# Hheld-Sheet1.net
KiCad netlist of a schematic drawn in Altium Designer
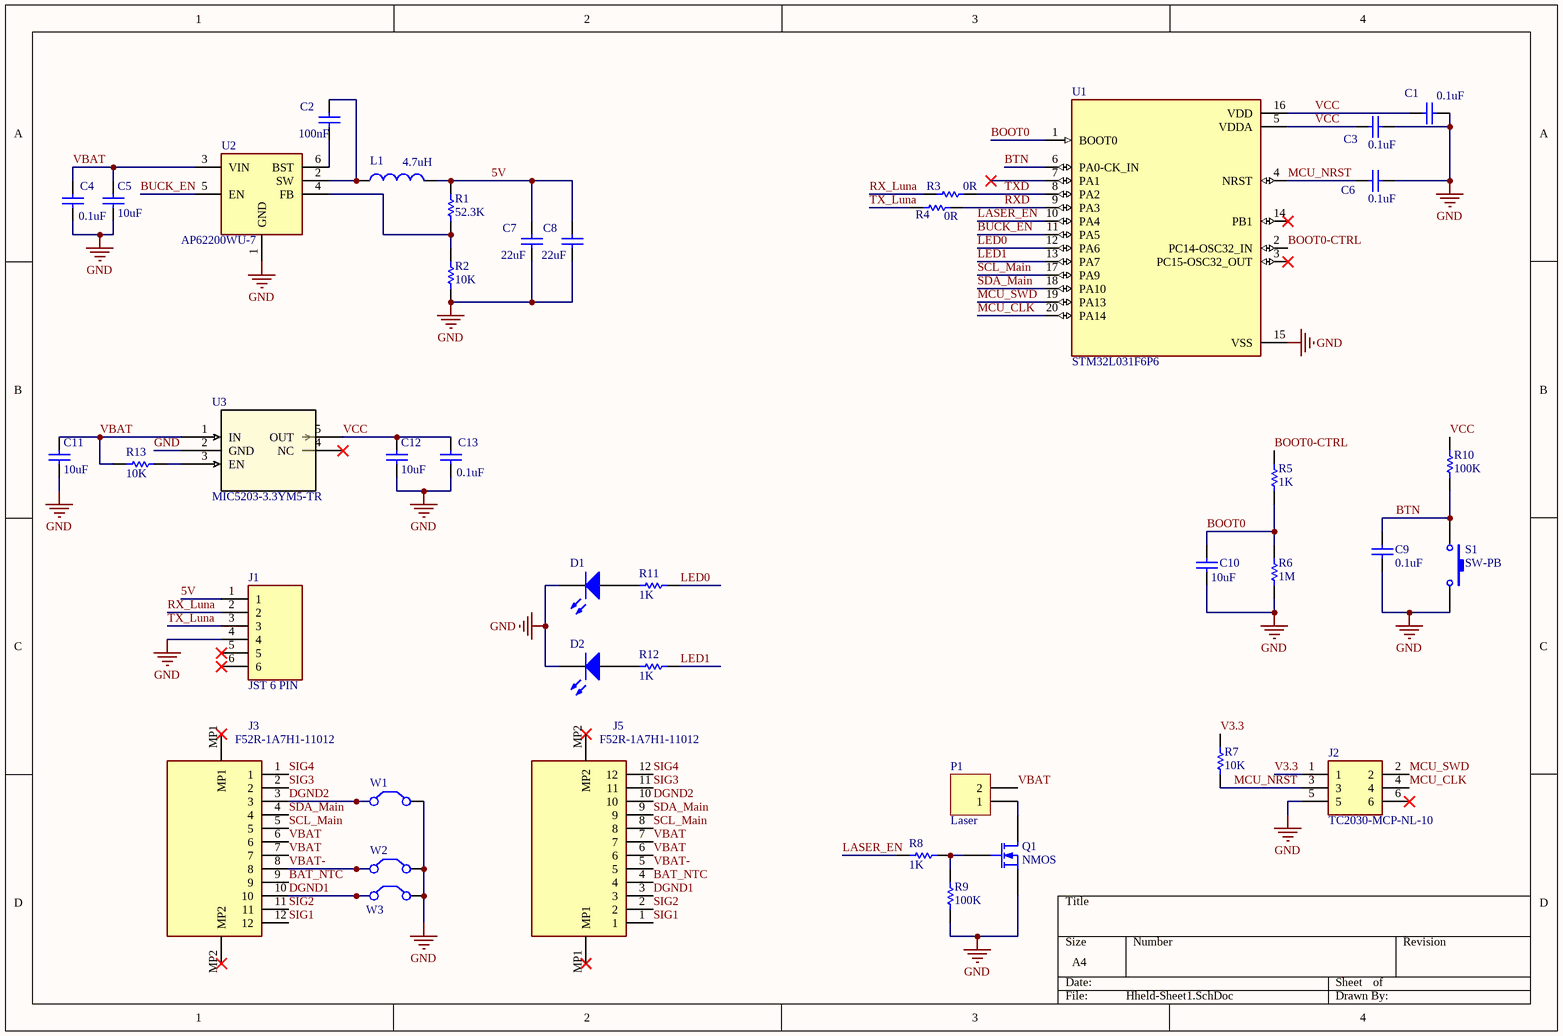
[diagram p0: Hheld-Sheet1.SchDoc]

(export (version "E")
  (design (tool "Eeschema 10.0.6"))
  (components
    (comp (ref "C1")
      (value "0.1uF")
      (footprint "Miscellaneous Devices:0402")
      (description "Capacitor")
      (fields (field (name "PUBLISHER") "Altium Limited"))
      (libsource (lib "Miscellaneous Devices") (part "Cap"))
    )
    (comp (ref "C2")
      (value "100nF")
      (footprint "Miscellaneous Devices:0402")
      (description "Capacitor")
      (fields (field (name "PUBLISHER") "Altium Limited"))
      (libsource (lib "Miscellaneous Devices") (part "Cap"))
    )
    (comp (ref "C3")
      (value "0.1uF")
      (footprint "Miscellaneous Devices:0402")
      (description "Capacitor")
      (fields (field (name "PUBLISHER") "Altium Limited"))
      (libsource (lib "Miscellaneous Devices") (part "Cap"))
    )
    (comp (ref "C4")
      (value "0.1uF")
      (footprint "Miscellaneous Devices:0402")
      (description "Capacitor")
      (fields (field (name "PUBLISHER") "Altium Limited"))
      (libsource (lib "Miscellaneous Devices") (part "Cap"))
    )
    (comp (ref "C5")
      (value "10uF")
      (footprint "Miscellaneous Devices:6-0805_L")
      (description "Capacitor")
      (fields (field (name "PUBLISHER") "Altium Limited"))
      (libsource (lib "Miscellaneous Devices") (part "Cap"))
    )
    (comp (ref "C6")
      (value "0.1uF")
      (footprint "Miscellaneous Devices:0402")
      (description "Capacitor")
      (fields (field (name "PUBLISHER") "Altium Limited"))
      (libsource (lib "Miscellaneous Devices") (part "Cap"))
    )
    (comp (ref "C7")
      (value "22uF")
      (footprint "Miscellaneous Devices:6-0805_L")
      (description "Capacitor")
      (fields (field (name "PUBLISHER") "Altium Limited"))
      (libsource (lib "Miscellaneous Devices") (part "Cap"))
    )
    (comp (ref "C8")
      (value "22uF")
      (footprint "Miscellaneous Devices:6-0805_L")
      (description "Capacitor")
      (fields (field (name "PUBLISHER") "Altium Limited"))
      (libsource (lib "Miscellaneous Devices") (part "Cap"))
    )
    (comp (ref "C9")
      (value "0.1uF")
      (footprint "Miscellaneous Devices:0402")
      (description "Capacitor")
      (fields (field (name "PUBLISHER") "Altium Limited"))
      (libsource (lib "Miscellaneous Devices") (part "Cap"))
    )
    (comp (ref "C10")
      (value "10uF")
      (footprint "Miscellaneous Devices:6-0805_L")
      (description "Capacitor")
      (fields (field (name "PUBLISHER") "Altium Limited"))
      (libsource (lib "Miscellaneous Devices") (part "Cap"))
    )
    (comp (ref "C11")
      (value "10uF")
      (footprint "Miscellaneous Devices:6-0805_L")
      (description "Capacitor")
      (fields (field (name "PUBLISHER") "Altium Limited"))
      (libsource (lib "Miscellaneous Devices") (part "Cap"))
    )
    (comp (ref "C12")
      (value "10uF")
      (footprint "Miscellaneous Devices:6-0805_L")
      (description "Capacitor")
      (fields (field (name "PUBLISHER") "Altium Limited"))
      (libsource (lib "Miscellaneous Devices") (part "Cap"))
    )
    (comp (ref "C13")
      (value "0.1uF")
      (footprint "Miscellaneous Devices:0402")
      (description "Capacitor")
      (fields (field (name "PUBLISHER") "Altium Limited"))
      (libsource (lib "Miscellaneous Devices") (part "Cap"))
    )
    (comp (ref "D1")
      (value "~")
      (footprint "1608[0603]")
      (description "Typical INFRARED GaAs LED")
      (fields (field (name "PUBLISHER") "Altium Limited"))
      (libsource (lib "Miscellaneous Devices") (part "LED0"))
    )
    (comp (ref "D2")
      (value "~")
      (footprint "1608[0603]")
      (description "Typical INFRARED GaAs LED")
      (fields (field (name "PUBLISHER") "Altium Limited"))
      (libsource (lib "Miscellaneous Devices") (part "LED0"))
    )
    (comp (ref "J1")
      (value "JST 6 PIN")
      (footprint "SHDRRA6W50P0X200_1X6_1390X760X480P")
      (description "Connector")
      (fields (field (name "MANUFACTURER_PART_NUMBER") "S6B-PH-K-S(LF)(SN)"))
      (libsource (lib "S6B-PH-K-S(LF)(SN) JST 6PIN") (part "S6B-PH-K-S_LF__SN_"))
    )
    (comp (ref "J2")
      (value "TC2030-MCP-NL-10")
      (footprint "TC2030MCPNL10")
      (description "Connector")
      (libsource (lib "TC2030") (part "TC2030-MCP-NL-10"))
    )
    (comp (ref "J3")
      (value "F52R-1A7H1-11012")
      (footprint "F52R1A7H111012")
      (description "Connector")
      (libsource (lib "") (part "F52R-1A7H1-11012_1"))
    )
    (comp (ref "J5")
      (value "F52R-1A7H1-11012")
      (footprint "F52R1A7H111012")
      (description "Connector")
      (libsource (lib "F52R-1A7H1-11012 FPC") (part "F52R-1A7H1-11012"))
    )
    (comp (ref "L1")
      (value "4.7uH")
      (footprint "TYS50404R7N-10 inductor:TYS50404R7N10")
      (description "Inductor")
      (fields (field (name "PUBLISHER") "Altium Limited"))
      (libsource (lib "Miscellaneous Devices") (part "Inductor"))
    )
    (comp (ref "P1")
      (value "Laser")
      (footprint "MHDR1X2")
      (description "Header, 2-Pin")
      (fields (field (name "PUBLISHER") "Altium Limited"))
      (libsource (lib "Miscellaneous Connectors") (part "MHDR1X2"))
    )
    (comp (ref "Q1")
      (value "NMOS")
      (footprint "SOT65P210X100-3N")
      (description "N-Channel MOSFETBSS214NWH6327XTSA1")
      (fields (field (name "PUBLISHER") "Altium Limited"))
      (libsource (lib "Miscellaneous Devices") (part "MOSFET-N"))
    )
    (comp (ref "R1")
      (value "52.3K")
      (footprint "Miscellaneous Devices:0402")
      (description "Semiconductor Resistor")
      (fields (field (name "PUBLISHER") "Altium Limited"))
      (libsource (lib "Miscellaneous Devices") (part "Res Semi"))
    )
    (comp (ref "R2")
      (value "10K")
      (footprint "Miscellaneous Devices:0402")
      (description "Semiconductor Resistor")
      (fields (field (name "PUBLISHER") "Altium Limited"))
      (libsource (lib "Miscellaneous Devices") (part "Res Semi"))
    )
    (comp (ref "R3")
      (value "0R")
      (footprint "Miscellaneous Devices:0402")
      (description "Semiconductor Resistor")
      (fields (field (name "PUBLISHER") "Altium Limited"))
      (libsource (lib "Miscellaneous Devices") (part "Res Semi"))
    )
    (comp (ref "R4")
      (value "0R")
      (footprint "Miscellaneous Devices:0402")
      (description "Semiconductor Resistor")
      (fields (field (name "PUBLISHER") "Altium Limited"))
      (libsource (lib "Miscellaneous Devices") (part "Res Semi"))
    )
    (comp (ref "R5")
      (value "1K")
      (footprint "Miscellaneous Devices:0402")
      (description "Semiconductor Resistor")
      (fields (field (name "PUBLISHER") "Altium Limited"))
      (libsource (lib "Miscellaneous Devices") (part "Res Semi"))
    )
    (comp (ref "R6")
      (value "1M")
      (footprint "Miscellaneous Devices:0402")
      (description "Semiconductor Resistor")
      (fields (field (name "PUBLISHER") "Altium Limited"))
      (libsource (lib "Miscellaneous Devices") (part "Res Semi"))
    )
    (comp (ref "R7")
      (value "10K")
      (footprint "Miscellaneous Devices:0402")
      (description "Semiconductor Resistor")
      (fields (field (name "PUBLISHER") "Altium Limited"))
      (libsource (lib "Miscellaneous Devices") (part "Res Semi"))
    )
    (comp (ref "R8")
      (value "1K")
      (footprint "Miscellaneous Devices:0402")
      (description "Semiconductor Resistor")
      (fields (field (name "PUBLISHER") "Altium Limited"))
      (libsource (lib "Miscellaneous Devices") (part "Res Semi"))
    )
    (comp (ref "R9")
      (value "100K")
      (footprint "Miscellaneous Devices:0402")
      (description "Semiconductor Resistor")
      (fields (field (name "PUBLISHER") "Altium Limited"))
      (libsource (lib "Miscellaneous Devices") (part "Res Semi"))
    )
    (comp (ref "R10")
      (value "100K")
      (footprint "Miscellaneous Devices:0402")
      (description "Semiconductor Resistor")
      (fields (field (name "PUBLISHER") "Altium Limited"))
      (libsource (lib "Miscellaneous Devices") (part "Res Semi"))
    )
    (comp (ref "R11")
      (value "1K")
      (footprint "Miscellaneous Devices:0402")
      (description "Semiconductor Resistor")
      (fields (field (name "PUBLISHER") "Altium Limited"))
      (libsource (lib "Miscellaneous Devices") (part "Res Semi"))
    )
    (comp (ref "R12")
      (value "1K")
      (footprint "Miscellaneous Devices:0402")
      (description "Semiconductor Resistor")
      (fields (field (name "PUBLISHER") "Altium Limited"))
      (libsource (lib "Miscellaneous Devices") (part "Res Semi"))
    )
    (comp (ref "R13")
      (value "10K")
      (footprint "Miscellaneous Devices:0402")
      (description "Semiconductor Resistor")
      (fields (field (name "PUBLISHER") "Altium Limited"))
      (libsource (lib "Miscellaneous Devices") (part "Res Semi"))
    )
    (comp (ref "S1")
      (value "SW-PB")
      (footprint "430456085736")
      (description "Switch")
      (fields (field (name "PUBLISHER") "Altium Limited"))
      (libsource (lib "Miscellaneous Devices") (part "SW-PB"))
    )
    (comp (ref "U1")
      (value "STM32L031F6P6")
      (footprint "SOP65P640X120-20N")
      (description "Ultra-low-power ARM Cortex-M0+ MCU with 32-Kbytes Flash, 32 MHz CPU")
      (fields (field (name "MF") "{'manufacturer': u'STMicroelectronics'}"))
      (libsource (lib "*") (part "STM32L031F6P6"))
    )
    (comp (ref "U2")
      (value "AP62200WU-7")
      (footprint "SOT95P280X100-6N")
      (description "Integrated Circuit")
      (fields (field (name "MOUSER PART NUMBER") "621-AP62200WU-7"))
      (libsource (lib "AP62200WU-7 DC-DC") (part "AP62200WU-7"))
    )
    (comp (ref "U3")
      (value "MIC5203-3.3YM5-TR")
      (footprint "SOT-23-5_M5_MCH")
      (description "No Description Available")
      (fields (field (name "COPYRIGHT") "Copyright (C) 2022 Ultra Librarian. All rights reserved."))
      (libsource (lib "MIC5203-3P3YM5-TR") (part "MIC5203-3.3YM5-TR"))
    )
    (comp (ref "W1")
      (value "~")
      (footprint "0402")
      (description "Jumper Wire")
      (fields (field (name "PUBLISHER") "Altium Limited"))
      (libsource (lib "Miscellaneous Devices") (part "Jumper"))
    )
    (comp (ref "W2")
      (value "~")
      (footprint "0402")
      (description "Jumper Wire")
      (fields (field (name "PUBLISHER") "Altium Limited"))
      (libsource (lib "Miscellaneous Devices") (part "Jumper"))
    )
    (comp (ref "W3")
      (value "~")
      (footprint "0402")
      (description "Jumper Wire")
      (fields (field (name "PUBLISHER") "Altium Limited"))
      (libsource (lib "Miscellaneous Devices") (part "Jumper"))
    )
  )
  (nets
    (net (code "1") (name "/5V") (class "Default")
      (node (ref "C7") (pin "1") (pinfunction "1_1") (pintype "passive"))
      (node (ref "C8") (pin "1") (pinfunction "1_1") (pintype "passive"))
      (node (ref "J1") (pin "1") (pinfunction "1_1") (pintype "passive"))
      (node (ref "L1") (pin "2") (pinfunction "2_2") (pintype "passive"))
      (node (ref "R1") (pin "2") (pinfunction "2_2") (pintype "passive"))
    )
    (net (code "2") (name "/BAT_NTC") (class "Default")
      (node (ref "J3") (pin "9") (pinfunction "9_9") (pintype "passive"))
      (node (ref "J5") (pin "4") (pinfunction "4_4") (pintype "passive"))
    )
    (net (code "3") (name "/BOOT0") (class "Default")
      (node (ref "C10") (pin "2") (pinfunction "2_2") (pintype "passive"))
      (node (ref "R5") (pin "1") (pinfunction "1_1") (pintype "passive"))
      (node (ref "R6") (pin "2") (pinfunction "2_2") (pintype "passive"))
      (node (ref "U1") (pin "1") (pinfunction "BOOT0_1") (pintype "input"))
    )
    (net (code "4") (name "/BOOT0-CTRL") (class "Default")
      (node (ref "R5") (pin "2") (pinfunction "2_2") (pintype "passive"))
      (node (ref "U1") (pin "2") (pinfunction "PC14-OSC32_IN_2") (pintype "bidirectional"))
    )
    (net (code "5") (name "/BTN") (class "Default")
      (node (ref "C9") (pin "1") (pinfunction "1_1") (pintype "passive"))
      (node (ref "R10") (pin "1") (pinfunction "1_1") (pintype "passive"))
      (node (ref "S1") (pin "1") (pinfunction "1_1") (pintype "passive"))
      (node (ref "U1") (pin "6") (pinfunction "PA0-CK_IN_6") (pintype "bidirectional"))
    )
    (net (code "6") (name "/BUCK_EN") (class "Default")
      (node (ref "U1") (pin "11") (pinfunction "PA5_11") (pintype "bidirectional"))
      (node (ref "U2") (pin "5") (pinfunction "EN_5") (pintype "passive"))
    )
    (net (code "7") (name "/DGND1") (class "Default")
      (node (ref "J3") (pin "10") (pinfunction "10_10") (pintype "passive"))
      (node (ref "J5") (pin "3") (pinfunction "3_3") (pintype "passive"))
      (node (ref "W3") (pin "1") (pinfunction "C1_1") (pintype "passive"))
    )
    (net (code "8") (name "/DGND2") (class "Default")
      (node (ref "J3") (pin "3") (pinfunction "3_3") (pintype "passive"))
      (node (ref "J5") (pin "10") (pinfunction "10_10") (pintype "passive"))
      (node (ref "W1") (pin "1") (pinfunction "C1_1") (pintype "passive"))
    )
    (net (code "9") (name "/LASER_EN") (class "Default")
      (node (ref "R8") (pin "1") (pinfunction "1_1") (pintype "passive"))
      (node (ref "U1") (pin "10") (pinfunction "PA4_10") (pintype "bidirectional"))
    )
    (net (code "10") (name "/LED0") (class "Default")
      (node (ref "R11") (pin "2") (pinfunction "2_2") (pintype "passive"))
      (node (ref "U1") (pin "12") (pinfunction "PA6_12") (pintype "bidirectional"))
    )
    (net (code "11") (name "/LED1") (class "Default")
      (node (ref "R12") (pin "2") (pinfunction "2_2") (pintype "passive"))
      (node (ref "U1") (pin "13") (pinfunction "PA7_13") (pintype "bidirectional"))
    )
    (net (code "12") (name "/MCU_CLK") (class "Default")
      (node (ref "J2") (pin "4") (pinfunction "4_4") (pintype "passive"))
      (node (ref "U1") (pin "20") (pinfunction "PA14_20") (pintype "bidirectional"))
    )
    (net (code "13") (name "/MCU_NRST") (class "Default")
      (node (ref "C6") (pin "1") (pinfunction "1_1") (pintype "passive"))
      (node (ref "J2") (pin "3") (pinfunction "3_3") (pintype "passive"))
      (node (ref "R7") (pin "1") (pinfunction "1_1") (pintype "passive"))
      (node (ref "U1") (pin "4") (pinfunction "NRST_4") (pintype "bidirectional"))
    )
    (net (code "14") (name "/MCU_SWD") (class "Default")
      (node (ref "J2") (pin "2") (pinfunction "2_2") (pintype "passive"))
      (node (ref "U1") (pin "19") (pinfunction "PA13_19") (pintype "bidirectional"))
    )
    (net (code "15") (name "/RXD") (class "Default")
      (node (ref "R4") (pin "1") (pinfunction "1_1") (pintype "passive"))
      (node (ref "U1") (pin "9") (pinfunction "PA3_9") (pintype "bidirectional"))
    )
    (net (code "16") (name "/RX_Luna") (class "Default")
      (node (ref "J1") (pin "2") (pinfunction "2_2") (pintype "passive"))
      (node (ref "R3") (pin "2") (pinfunction "2_2") (pintype "passive"))
    )
    (net (code "17") (name "/SCL_Main") (class "Default")
      (node (ref "J3") (pin "5") (pinfunction "5_5") (pintype "passive"))
      (node (ref "J5") (pin "8") (pinfunction "8_8") (pintype "passive"))
      (node (ref "U1") (pin "17") (pinfunction "PA9_17") (pintype "bidirectional"))
    )
    (net (code "18") (name "/SDA_Main") (class "Default")
      (node (ref "J3") (pin "4") (pinfunction "4_4") (pintype "passive"))
      (node (ref "J5") (pin "9") (pinfunction "9_9") (pintype "passive"))
      (node (ref "U1") (pin "18") (pinfunction "PA10_18") (pintype "bidirectional"))
    )
    (net (code "19") (name "/SIG1") (class "Default")
      (node (ref "J3") (pin "12") (pinfunction "12_12") (pintype "passive"))
      (node (ref "J5") (pin "1") (pinfunction "1_1") (pintype "passive"))
    )
    (net (code "20") (name "/SIG2") (class "Default")
      (node (ref "J3") (pin "11") (pinfunction "11_11") (pintype "passive"))
      (node (ref "J5") (pin "2") (pinfunction "2_2") (pintype "passive"))
    )
    (net (code "21") (name "/SIG3") (class "Default")
      (node (ref "J3") (pin "2") (pinfunction "2_2") (pintype "passive"))
      (node (ref "J5") (pin "11") (pinfunction "11_11") (pintype "passive"))
    )
    (net (code "22") (name "/SIG4") (class "Default")
      (node (ref "J3") (pin "1") (pinfunction "1_1") (pintype "passive"))
      (node (ref "J5") (pin "12") (pinfunction "12_12") (pintype "passive"))
    )
    (net (code "23") (name "/TXD") (class "Default")
      (node (ref "R3") (pin "1") (pinfunction "1_1") (pintype "passive"))
      (node (ref "U1") (pin "8") (pinfunction "PA2_8") (pintype "bidirectional"))
    )
    (net (code "24") (name "/TX_Luna") (class "Default")
      (node (ref "J1") (pin "3") (pinfunction "3_3") (pintype "passive"))
      (node (ref "R4") (pin "2") (pinfunction "2_2") (pintype "passive"))
    )
    (net (code "25") (name "/V3.3") (class "Default")
      (node (ref "J2") (pin "1") (pinfunction "1_1") (pintype "passive"))
      (node (ref "R7") (pin "2") (pinfunction "2_2") (pintype "passive"))
    )
    (net (code "26") (name "/VBAT") (class "Default")
      (node (ref "C11") (pin "2") (pinfunction "2_2") (pintype "passive"))
      (node (ref "C4") (pin "2") (pinfunction "2_2") (pintype "passive"))
      (node (ref "C5") (pin "2") (pinfunction "2_2") (pintype "passive"))
      (node (ref "J3") (pin "6") (pinfunction "6_6") (pintype "passive"))
      (node (ref "J3") (pin "7") (pinfunction "7_7") (pintype "passive"))
      (node (ref "J5") (pin "6") (pinfunction "6_6") (pintype "passive"))
      (node (ref "J5") (pin "7") (pinfunction "7_7") (pintype "passive"))
      (node (ref "P1") (pin "2") (pinfunction "2_2") (pintype "passive"))
      (node (ref "R13") (pin "1") (pinfunction "1_1") (pintype "passive"))
      (node (ref "U2") (pin "3") (pinfunction "VIN_3") (pintype "passive"))
      (node (ref "U3") (pin "1") (pinfunction "IN_1") (pintype "input"))
    )
    (net (code "27") (name "/VBAT-") (class "Default")
      (node (ref "J3") (pin "8") (pinfunction "8_8") (pintype "passive"))
      (node (ref "J5") (pin "5") (pinfunction "5_5") (pintype "passive"))
      (node (ref "W2") (pin "1") (pinfunction "C1_1") (pintype "passive"))
    )
    (net (code "28") (name "/VCC") (class "Default")
      (node (ref "C1") (pin "1") (pinfunction "1_1") (pintype "passive"))
      (node (ref "C12") (pin "2") (pinfunction "2_2") (pintype "passive"))
      (node (ref "C13") (pin "2") (pinfunction "2_2") (pintype "passive"))
      (node (ref "C3") (pin "1") (pinfunction "1_1") (pintype "passive"))
      (node (ref "R10") (pin "2") (pinfunction "2_2") (pintype "passive"))
      (node (ref "U1") (pin "16") (pinfunction "VDD_16") (pintype "power_in"))
      (node (ref "U1") (pin "5") (pinfunction "VDDA_5") (pintype "power_in"))
      (node (ref "U3") (pin "5") (pinfunction "OUT_5") (pintype "passive"))
    )
    (net (code "29") (name "GND") (class "Default")
      (node (ref "C1") (pin "2") (pinfunction "2_2") (pintype "passive"))
      (node (ref "C10") (pin "1") (pinfunction "1_1") (pintype "passive"))
      (node (ref "C11") (pin "1") (pinfunction "1_1") (pintype "passive"))
      (node (ref "C12") (pin "1") (pinfunction "1_1") (pintype "passive"))
      (node (ref "C13") (pin "1") (pinfunction "1_1") (pintype "passive"))
      (node (ref "C3") (pin "2") (pinfunction "2_2") (pintype "passive"))
      (node (ref "C4") (pin "1") (pinfunction "1_1") (pintype "passive"))
      (node (ref "C5") (pin "1") (pinfunction "1_1") (pintype "passive"))
      (node (ref "C6") (pin "2") (pinfunction "2_2") (pintype "passive"))
      (node (ref "C7") (pin "2") (pinfunction "2_2") (pintype "passive"))
      (node (ref "C8") (pin "2") (pinfunction "2_2") (pintype "passive"))
      (node (ref "C9") (pin "2") (pinfunction "2_2") (pintype "passive"))
      (node (ref "D1") (pin "2") (pinfunction "K_2") (pintype "passive"))
      (node (ref "D2") (pin "2") (pinfunction "K_2") (pintype "passive"))
      (node (ref "J1") (pin "4") (pinfunction "4_4") (pintype "passive"))
      (node (ref "J2") (pin "5") (pinfunction "5_5") (pintype "passive"))
      (node (ref "Q1") (pin "3") (pinfunction "S_3") (pintype "passive"))
      (node (ref "R2") (pin "2") (pinfunction "2_2") (pintype "passive"))
      (node (ref "R6") (pin "1") (pinfunction "1_1") (pintype "passive"))
      (node (ref "R9") (pin "1") (pinfunction "1_1") (pintype "passive"))
      (node (ref "S1") (pin "2") (pinfunction "2_2") (pintype "passive"))
      (node (ref "U1") (pin "15") (pinfunction "VSS_15") (pintype "power_in"))
      (node (ref "U2") (pin "1") (pinfunction "GND_1") (pintype "passive"))
      (node (ref "U3") (pin "2") (pinfunction "GND_2") (pintype "power_in"))
      (node (ref "W1") (pin "2") (pinfunction "C2_2") (pintype "passive"))
      (node (ref "W2") (pin "2") (pinfunction "C2_2") (pintype "passive"))
      (node (ref "W3") (pin "2") (pinfunction "C2_2") (pintype "passive"))
    )
    (net (code "30") (name "Net-(D1-A)") (class "Default")
      (node (ref "D1") (pin "1") (pinfunction "A_1") (pintype "passive"))
      (node (ref "R11") (pin "1") (pinfunction "1_1") (pintype "passive"))
    )
    (net (code "31") (name "Net-(D2-A)") (class "Default")
      (node (ref "D2") (pin "1") (pinfunction "A_1") (pintype "passive"))
      (node (ref "R12") (pin "1") (pinfunction "1_1") (pintype "passive"))
    )
    (net (code "32") (name "Net-(Q1-D)") (class "Default")
      (node (ref "P1") (pin "1") (pinfunction "1_1") (pintype "passive"))
      (node (ref "Q1") (pin "1") (pinfunction "D_1") (pintype "passive"))
    )
    (net (code "33") (name "Net-(Q1-G)") (class "Default")
      (node (ref "Q1") (pin "2") (pinfunction "G_2") (pintype "passive"))
      (node (ref "R8") (pin "2") (pinfunction "2_2") (pintype "passive"))
      (node (ref "R9") (pin "2") (pinfunction "2_2") (pintype "passive"))
    )
    (net (code "34") (name "Net-(U2-BST)") (class "Default")
      (node (ref "C2") (pin "2") (pinfunction "2_2") (pintype "passive"))
      (node (ref "U2") (pin "6") (pinfunction "BST_6") (pintype "passive"))
    )
    (net (code "35") (name "Net-(U2-FB)") (class "Default")
      (node (ref "R1") (pin "1") (pinfunction "1_1") (pintype "passive"))
      (node (ref "R2") (pin "1") (pinfunction "1_1") (pintype "passive"))
      (node (ref "U2") (pin "4") (pinfunction "FB_4") (pintype "passive"))
    )
    (net (code "36") (name "Net-(U2-SW)") (class "Default")
      (node (ref "C2") (pin "1") (pinfunction "1_1") (pintype "passive"))
      (node (ref "L1") (pin "1") (pinfunction "1_1") (pintype "passive"))
      (node (ref "U2") (pin "2") (pinfunction "SW_2") (pintype "passive"))
    )
    (net (code "37") (name "Net-(U3-EN)") (class "Default")
      (node (ref "R13") (pin "2") (pinfunction "2_2") (pintype "passive"))
      (node (ref "U3") (pin "3") (pinfunction "EN_3") (pintype "input"))
    )
    (net (code "38") (name "unconnected-(J1-Pad5)") (class "Default")
      (node (ref "J1") (pin "5") (pinfunction "5_5") (pintype "passive+no_connect"))
    )
    (net (code "39") (name "unconnected-(J1-Pad6)") (class "Default")
      (node (ref "J1") (pin "6") (pinfunction "6_6") (pintype "passive+no_connect"))
    )
    (net (code "40") (name "unconnected-(J2-Pad6)") (class "Default")
      (node (ref "J2") (pin "6") (pinfunction "6_6") (pintype "passive+no_connect"))
    )
    (net (code "41") (name "unconnected-(J3-PadMP1)") (class "Default")
      (node (ref "J3") (pin "MP1") (pinfunction "MP1_MP1") (pintype "passive+no_connect"))
    )
    (net (code "42") (name "unconnected-(J3-PadMP2)") (class "Default")
      (node (ref "J3") (pin "MP2") (pinfunction "MP2_MP2") (pintype "passive+no_connect"))
    )
    (net (code "43") (name "unconnected-(J5-PadMP1)") (class "Default")
      (node (ref "J5") (pin "MP1") (pinfunction "MP1_MP1") (pintype "passive+no_connect"))
    )
    (net (code "44") (name "unconnected-(J5-PadMP2)") (class "Default")
      (node (ref "J5") (pin "MP2") (pinfunction "MP2_MP2") (pintype "passive+no_connect"))
    )
    (net (code "45") (name "unconnected-(U1-PA1-Pad7)") (class "Default")
      (node (ref "U1") (pin "7") (pinfunction "PA1_7") (pintype "bidirectional+no_connect"))
    )
    (net (code "46") (name "unconnected-(U1-PB1-Pad14)") (class "Default")
      (node (ref "U1") (pin "14") (pinfunction "PB1_14") (pintype "bidirectional+no_connect"))
    )
    (net (code "47") (name "unconnected-(U1-PC15-OSC32_OUT-Pad3)") (class "Default")
      (node (ref "U1") (pin "3") (pinfunction "PC15-OSC32_OUT_3") (pintype "bidirectional+no_connect"))
    )
    (net (code "48") (name "unconnected-(U3-NC-Pad4)") (class "Default")
      (node (ref "U3") (pin "4") (pinfunction "NC_4") (pintype "passive+no_connect"))
    )
  )
)
